# LightSensorsButtons.net
KiCad netlist of a schematic drawn in Altium Designer
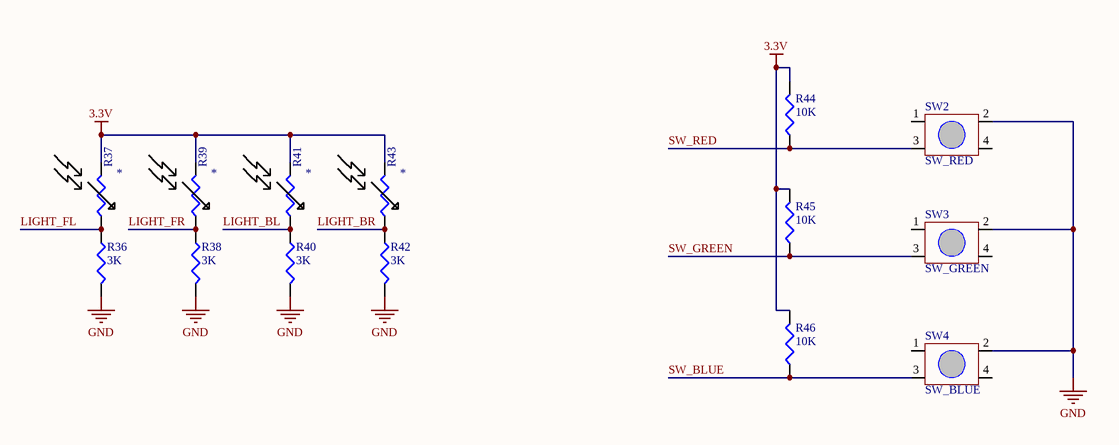
[diagram p0: LightSensorsButtons.SchDoc]

(export (version "E")
  (design (tool "Eeschema 10.0.6"))
  (components
    (comp (ref "R36")
      (value "3K")
      (footprint "RESC1608L")
      (description "Resistor")
      (fields
        (field (name "PART NUMBER") "RC0603FR-073KL")
        (field (name "MANUFACTURER") "Yageo")
        (field (name "PUBLISHER") "Altium Limited")
      )
      (libsource (lib "Miscellaneous Devices") (part "Res3"))
    )
    (comp (ref "R37")
      (value "photoresistor")
      (footprint "photoresistor")
      (fields
        (field (name "ALTIUM_VALUE") "*")
        (field (name "PART NUMBER") "PDV-P9103")
        (field (name "MANUFACTURER") "Advanced Photonix")
      )
      (libsource (lib "mrone") (part "photoresistor"))
    )
    (comp (ref "R38")
      (value "3K")
      (footprint "RESC1608L")
      (description "Resistor")
      (fields
        (field (name "PART NUMBER") "RC0603FR-073KL")
        (field (name "MANUFACTURER") "Yageo")
        (field (name "PUBLISHER") "Altium Limited")
      )
      (libsource (lib "Miscellaneous Devices") (part "Res3"))
    )
    (comp (ref "R39")
      (value "photoresistor")
      (footprint "photoresistor")
      (fields
        (field (name "ALTIUM_VALUE") "*")
        (field (name "PART NUMBER") "PDV-P9103")
        (field (name "MANUFACTURER") "Advanced Photonix")
      )
      (libsource (lib "mrone") (part "photoresistor"))
    )
    (comp (ref "R40")
      (value "3K")
      (footprint "RESC1608L")
      (description "Resistor")
      (fields
        (field (name "PART NUMBER") "RC0603FR-073KL")
        (field (name "MANUFACTURER") "Yageo")
        (field (name "PUBLISHER") "Altium Limited")
      )
      (libsource (lib "Miscellaneous Devices") (part "Res3"))
    )
    (comp (ref "R41")
      (value "photoresistor")
      (footprint "photoresistor")
      (fields
        (field (name "ALTIUM_VALUE") "*")
        (field (name "PART NUMBER") "PDV-P9103")
        (field (name "MANUFACTURER") "Advanced Photonix")
      )
      (libsource (lib "mrone") (part "photoresistor"))
    )
    (comp (ref "R42")
      (value "3K")
      (footprint "RESC1608L")
      (description "Resistor")
      (fields
        (field (name "PART NUMBER") "RC0603FR-073KL")
        (field (name "MANUFACTURER") "Yageo")
        (field (name "PUBLISHER") "Altium Limited")
      )
      (libsource (lib "Miscellaneous Devices") (part "Res3"))
    )
    (comp (ref "R43")
      (value "photoresistor")
      (footprint "photoresistor")
      (fields
        (field (name "ALTIUM_VALUE") "*")
        (field (name "PART NUMBER") "PDV-P9103")
        (field (name "MANUFACTURER") "Advanced Photonix")
      )
      (libsource (lib "mrone") (part "photoresistor"))
    )
    (comp (ref "R44")
      (value "10K")
      (footprint "RESC1608L")
      (description "Resistor")
      (fields
        (field (name "PART NUMBER") "SR03-1002")
        (field (name "MANUFACTURER") "Vishay")
        (field (name "PUBLISHER") "Altium Limited")
      )
      (libsource (lib "Miscellaneous Devices") (part "Res3"))
    )
    (comp (ref "R45")
      (value "10K")
      (footprint "RESC1608L")
      (description "Resistor")
      (fields
        (field (name "PART NUMBER") "SR03-1002")
        (field (name "MANUFACTURER") "Vishay")
        (field (name "PUBLISHER") "Altium Limited")
      )
      (libsource (lib "Miscellaneous Devices") (part "Res3"))
    )
    (comp (ref "R46")
      (value "10K")
      (footprint "RESC1608L")
      (description "Resistor")
      (fields
        (field (name "PART NUMBER") "SR03-1002")
        (field (name "MANUFACTURER") "Vishay")
        (field (name "PUBLISHER") "Altium Limited")
      )
      (libsource (lib "Miscellaneous Devices") (part "Res3"))
    )
    (comp (ref "SW2")
      (value "SW_RED")
      (footprint "SwitchTall-TL330")
      (fields (field (name "PART NUMBER") "EVQ-P0N02B") (field (name "MANUFACTURER") "Panasonic"))
      (libsource (lib "mrone") (part "Switch-TL330"))
    )
    (comp (ref "SW3")
      (value "SW_GREEN")
      (footprint "SwitchTall-TL330")
      (fields (field (name "PART NUMBER") "EVQ-P0N02B") (field (name "MANUFACTURER") "Panasonic"))
      (libsource (lib "mrone") (part "Switch-TL330"))
    )
    (comp (ref "SW4")
      (value "SW_BLUE")
      (footprint "SwitchTall-TL330")
      (fields (field (name "PART NUMBER") "EVQ-P0N02B") (field (name "MANUFACTURER") "Panasonic"))
      (libsource (lib "mrone") (part "Switch-TL330"))
    )
  )
  (nets
    (net (code "1") (name "/LIGHT_BL") (class "Default")
      (node (ref "R40") (pin "1") (pinfunction "1_1") (pintype "passive"))
      (node (ref "R41") (pin "1") (pinfunction "1_1") (pintype "passive"))
    )
    (net (code "2") (name "/LIGHT_BR") (class "Default")
      (node (ref "R42") (pin "1") (pinfunction "1_1") (pintype "passive"))
      (node (ref "R43") (pin "1") (pinfunction "1_1") (pintype "passive"))
    )
    (net (code "3") (name "/LIGHT_FL") (class "Default")
      (node (ref "R36") (pin "1") (pinfunction "1_1") (pintype "passive"))
      (node (ref "R37") (pin "1") (pinfunction "1_1") (pintype "passive"))
    )
    (net (code "4") (name "/LIGHT_FR") (class "Default")
      (node (ref "R38") (pin "1") (pinfunction "1_1") (pintype "passive"))
      (node (ref "R39") (pin "1") (pinfunction "1_1") (pintype "passive"))
    )
    (net (code "5") (name "/SW_BLUE") (class "Default")
      (node (ref "R46") (pin "1") (pinfunction "1_1") (pintype "passive"))
      (node (ref "SW4") (pin "3") (pinfunction "3_3") (pintype "passive"))
    )
    (net (code "6") (name "/SW_GREEN") (class "Default")
      (node (ref "R45") (pin "1") (pinfunction "1_1") (pintype "passive"))
      (node (ref "SW3") (pin "3") (pinfunction "3_3") (pintype "passive"))
    )
    (net (code "7") (name "/SW_RED") (class "Default")
      (node (ref "R44") (pin "1") (pinfunction "1_1") (pintype "passive"))
      (node (ref "SW2") (pin "3") (pinfunction "3_3") (pintype "passive"))
    )
    (net (code "8") (name "3.3V") (class "Default")
      (node (ref "R37") (pin "2") (pinfunction "2_2") (pintype "passive"))
      (node (ref "R39") (pin "2") (pinfunction "2_2") (pintype "passive"))
      (node (ref "R41") (pin "2") (pinfunction "2_2") (pintype "passive"))
      (node (ref "R43") (pin "2") (pinfunction "2_2") (pintype "passive"))
      (node (ref "R44") (pin "2") (pinfunction "2_2") (pintype "passive"))
      (node (ref "R45") (pin "2") (pinfunction "2_2") (pintype "passive"))
      (node (ref "R46") (pin "2") (pinfunction "2_2") (pintype "passive"))
    )
    (net (code "9") (name "GND") (class "Default")
      (node (ref "R36") (pin "2") (pinfunction "2_2") (pintype "passive"))
      (node (ref "R38") (pin "2") (pinfunction "2_2") (pintype "passive"))
      (node (ref "R40") (pin "2") (pinfunction "2_2") (pintype "passive"))
      (node (ref "R42") (pin "2") (pinfunction "2_2") (pintype "passive"))
      (node (ref "SW2") (pin "2") (pinfunction "2_2") (pintype "passive"))
      (node (ref "SW3") (pin "2") (pinfunction "2_2") (pintype "passive"))
      (node (ref "SW4") (pin "2") (pinfunction "2_2") (pintype "passive"))
    )
    (net (code "10") (name "unconnected-(SW2-Pad1)") (class "Default")
      (node (ref "SW2") (pin "1") (pinfunction "1_1") (pintype "passive"))
    )
    (net (code "11") (name "unconnected-(SW2-Pad4)") (class "Default")
      (node (ref "SW2") (pin "4") (pinfunction "4_4") (pintype "passive"))
    )
    (net (code "12") (name "unconnected-(SW3-Pad1)") (class "Default")
      (node (ref "SW3") (pin "1") (pinfunction "1_1") (pintype "passive"))
    )
    (net (code "13") (name "unconnected-(SW3-Pad4)") (class "Default")
      (node (ref "SW3") (pin "4") (pinfunction "4_4") (pintype "passive"))
    )
    (net (code "14") (name "unconnected-(SW4-Pad1)") (class "Default")
      (node (ref "SW4") (pin "1") (pinfunction "1_1") (pintype "passive"))
    )
    (net (code "15") (name "unconnected-(SW4-Pad4)") (class "Default")
      (node (ref "SW4") (pin "4") (pinfunction "4_4") (pintype "passive"))
    )
  )
)
